# AC_circuit.net
KiCad netlist of a schematic drawn in Altium Designer
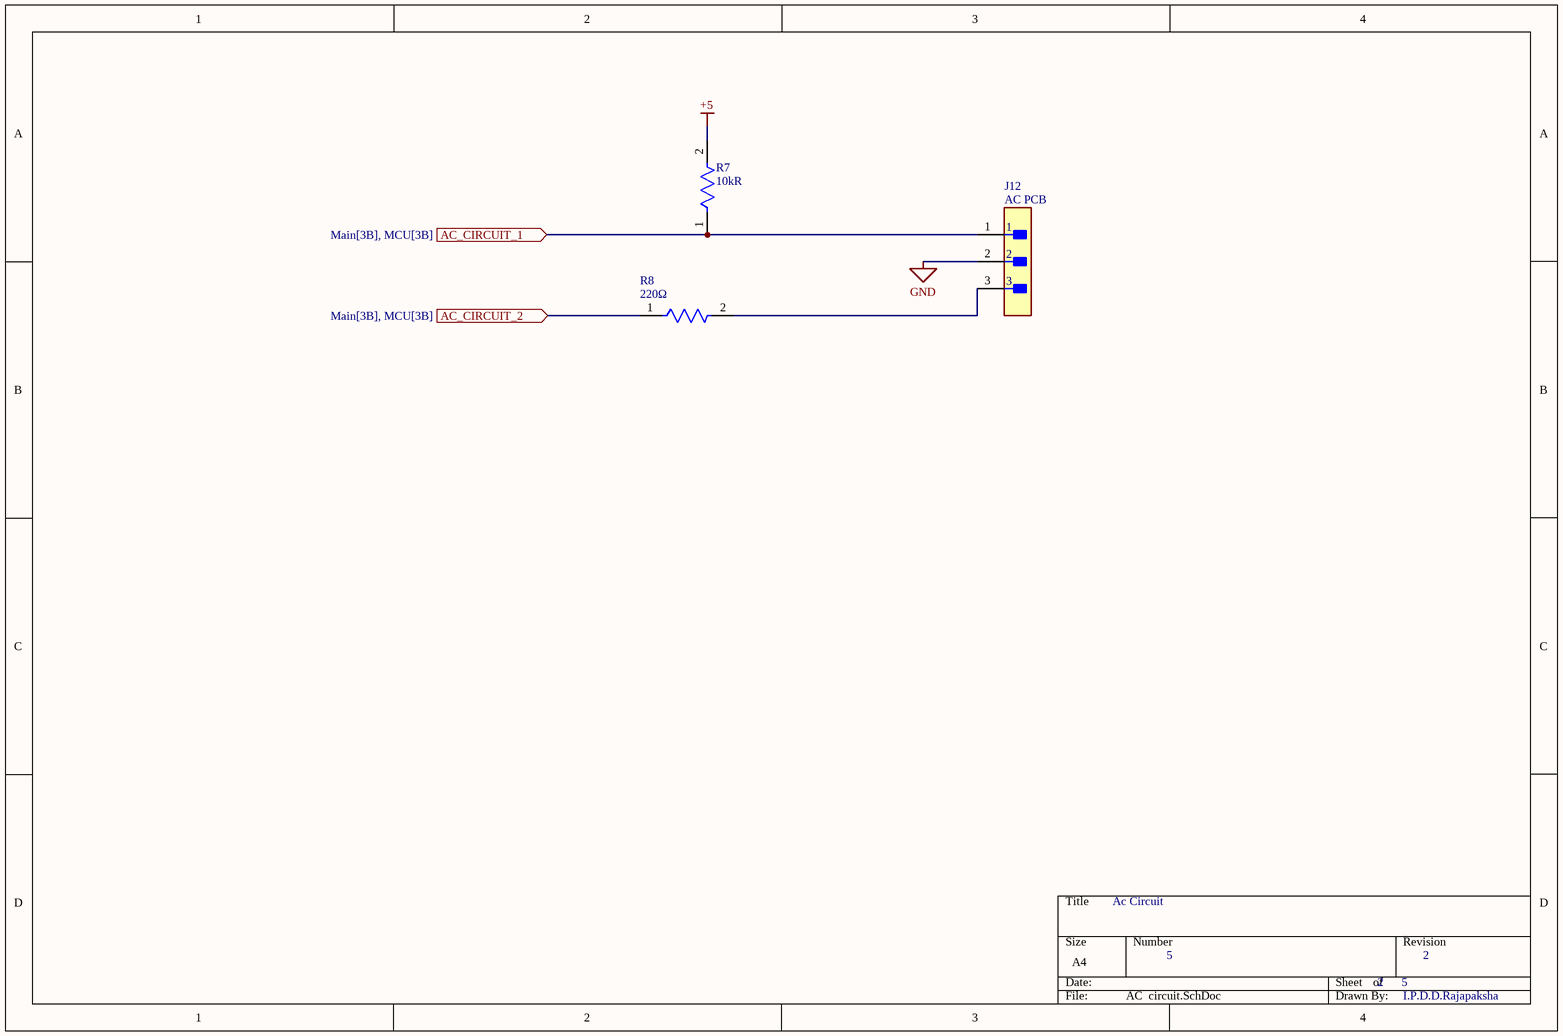
[diagram p0: AC  circuit.SchDoc]

(export (version "E")
  (design (tool "Eeschema 10.0.6"))
  (components
    (comp (ref "J12")
      (value "B3B-XH-A(LF)(SN)")
      (footprint "FP-B3B-XH-A_LF_SN-MFG")
      (description "CONN HEADER VERT 3POS 2.5MM")
      (fields (field (name "PARAMETER 1") "AC PCB"))
      (libsource (lib "Altium Content Vault") (part "0d3f023dd272f625e17a2be33dea85f"))
    )
    (comp (ref "R7")
      (value "CRCW120610K0FKEA")
      (footprint "FP-CRCW1206-e3-IPC_C")
      (description "RES Thick Film, 10kΩ, 1%, 0.25W, 100ppm/°C, 1206")
      (fields (field (name "TOLERANCE") "1%") (field (name "RESISTANCE") "10kR"))
      (libsource (lib "Altium Content Vault") (part "1029c3af85768c4190bb7ad29bc67b5"))
    )
    (comp (ref "R8")
      (value "220Ω")
      (footprint "FP-AC1206-MFG")
      (description "RES SMD 220 OHM 1% 1/4W 1206")
      (fields (field (name "TOLERANCE") "0.01") (field (name "MANUFACTURER") "Yageo"))
      (libsource (lib "Altium Content Vault") (part "1029c3af85768c4190bb7ad29bc67b5"))
    )
  )
  (nets
    (net (code "1") (name "+5") (class "Default")
      (node (ref "R7") (pin "2") (pinfunction "2_2") (pintype "passive"))
    )
    (net (code "2") (name "/AC_CIRCUIT_1") (class "Default")
      (node (ref "J12") (pin "1") (pinfunction "1_1") (pintype "passive"))
      (node (ref "R7") (pin "1") (pinfunction "1_1") (pintype "passive"))
    )
    (net (code "3") (name "/AC_CIRCUIT_2") (class "Default")
      (node (ref "R8") (pin "1") (pinfunction "1_1") (pintype "passive"))
    )
    (net (code "4") (name "GND") (class "Default")
      (node (ref "J12") (pin "2") (pinfunction "2_2") (pintype "passive"))
    )
    (net (code "5") (name "Net-(J12-Pad3)") (class "Default")
      (node (ref "J12") (pin "3") (pinfunction "3_3") (pintype "passive"))
      (node (ref "R8") (pin "2") (pinfunction "2_2") (pintype "passive"))
    )
  )
)
